# nuevo1.net
KiCad netlist of a schematic drawn in Altium Designer
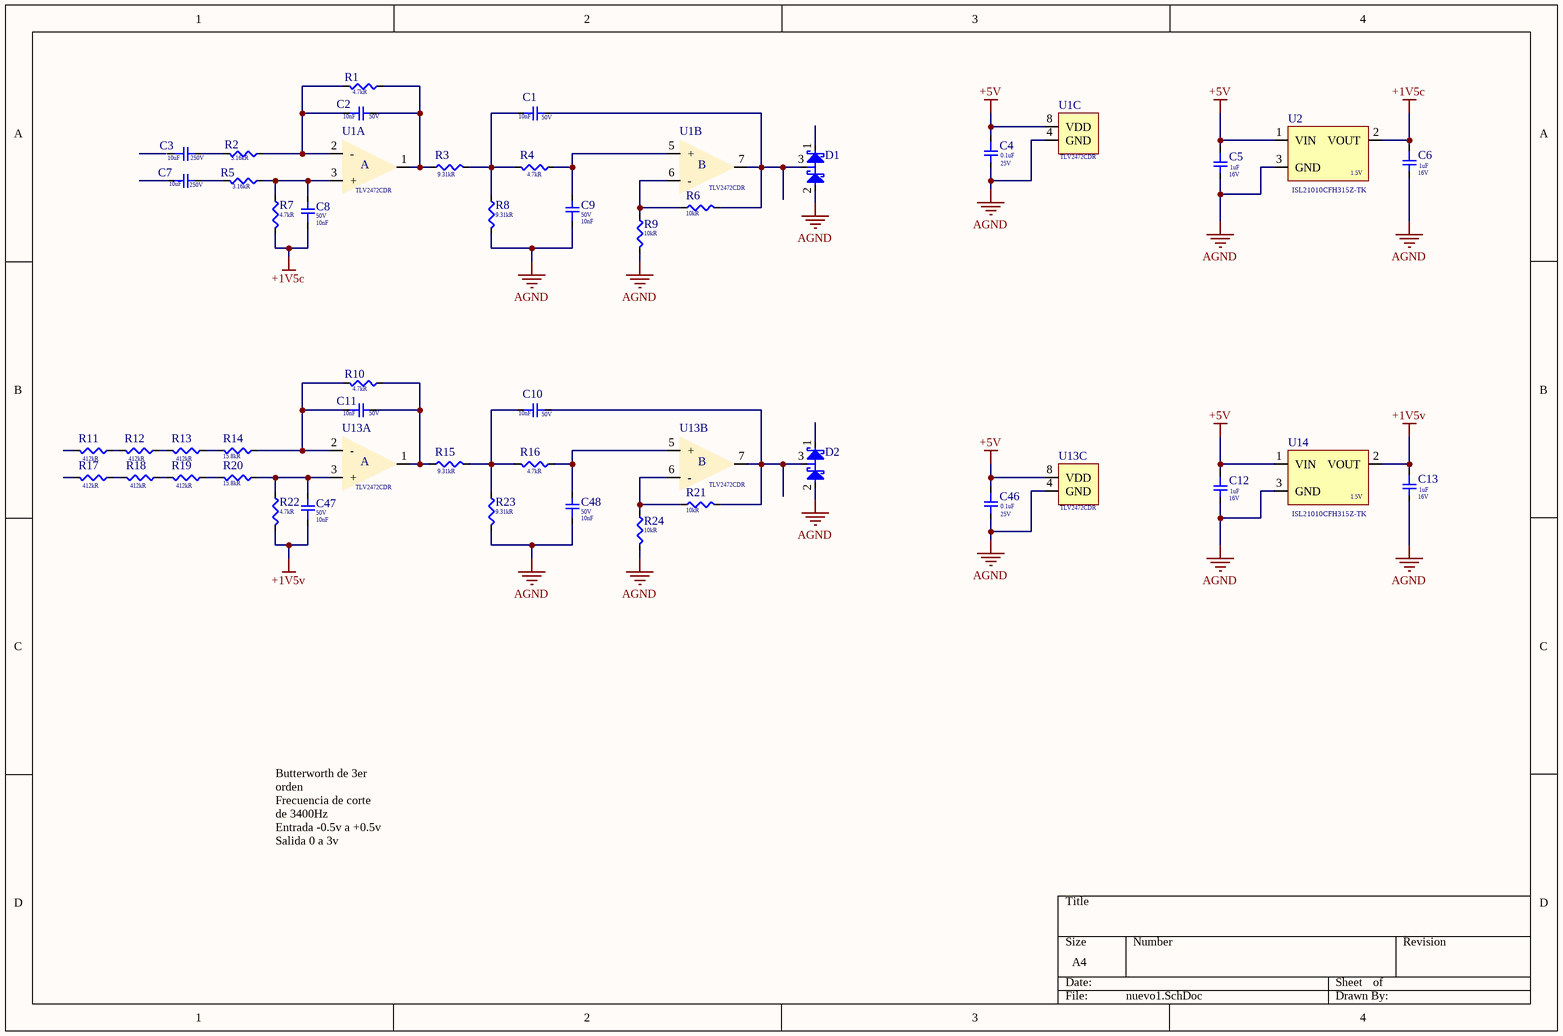
[diagram p0: nuevo1.SchDoc]

(export (version "E")
  (design (tool "Eeschema 10.0.6"))
  (components
    (comp (ref "C1")
      (value "CAP_GRM2195C1H103FA01D_MURATA")
      (footprint "CAP smd 0805")
      (description "0805 10 nF 50 V ±1% Tolerance C0G SMD Multilayer Ceramic Capacitor")
      (fields
        (field (name "TOLERANCE") "1%")
        (field (name "VOLTAGE") "50V")
        (field (name "CAPACITANCE") "10nF")
      )
      (libsource (lib "Cap") (part "CAP_GRM2195C1H103FA01D_MURATA"))
    )
    (comp (ref "C2")
      (value "CAP_GRM2195C1H103FA01D_MURATA")
      (footprint "CAP smd 0805")
      (description "0805 10 nF 50 V ±1% Tolerance C0G SMD Multilayer Ceramic Capacitor")
      (fields
        (field (name "TOLERANCE") "1%")
        (field (name "VOLTAGE") "50V")
        (field (name "CAPACITANCE") "10nF")
      )
      (libsource (lib "Cap") (part "CAP_GRM2195C1H103FA01D_MURATA"))
    )
    (comp (ref "C3")
      (value "CAP_B32754C2106K000")
      (footprint "Cap 22x36.5x31.5")
      (description "Cap Film 10uF 500V PP 10% (31.5 X 22 X 36.5mm) Dipped Radial 27.5mm 105°C Bulk")
      (fields
        (field (name "TOLERANCE") "10%")
        (field (name "VOLTAGE RATING (AC)") "250V")
        (field (name "CAPACITANCE") "10uF")
      )
      (libsource (lib "Cap") (part "CAP_B32754C2106K000"))
    )
    (comp (ref "C4")
      (value "CAP_CC0805KRX7R8BB104_YAGEO")
      (footprint "CAP smd 0805")
      (description "CAPACITOR, 0805, 100NF, 25V, REEL 4000")
      (fields
        (field (name "TOLERANCE") "10%")
        (field (name "VOLTAGE RATING") "25V")
        (field (name "CAPACITANCE") "0.1uF")
      )
      (libsource (lib "Cap") (part "CAP_CC0805KRX7R8BB104_YAGEO"))
    )
    (comp (ref "C5")
      (value "CAP_CC0805KKX7R7BB105_YAGEO")
      (footprint "CAP smd 0805")
      (description "YAGEO   CC0805KKX7R7BB105   CERAMIC CAPACITOR, 1UF, 16V, X7R, 10%, 0805")
      (fields
        (field (name "TOLERANCE") "10%")
        (field (name "VOLTAGE RATING") "16V")
        (field (name "CAPACITANCE") "1uF")
      )
      (libsource (lib "Cap") (part "CAP_CC0805KKX7R7BB105_YAGEO"))
    )
    (comp (ref "C6")
      (value "CAP_CC0805KKX7R7BB105_YAGEO")
      (footprint "CAP smd 0805")
      (description "YAGEO   CC0805KKX7R7BB105   CERAMIC CAPACITOR, 1UF, 16V, X7R, 10%, 0805")
      (fields
        (field (name "TOLERANCE") "10%")
        (field (name "VOLTAGE RATING") "16V")
        (field (name "CAPACITANCE") "1uF")
      )
      (libsource (lib "Cap") (part "CAP_CC0805KKX7R7BB105_YAGEO"))
    )
    (comp (ref "C7")
      (value "CAP_B32754C2106K000")
      (footprint "Cap 22x36.5x31.5")
      (description "Cap Film 10uF 500V PP 10% (31.5 X 22 X 36.5mm) Dipped Radial 27.5mm 105°C Bulk")
      (fields
        (field (name "TOLERANCE") "10%")
        (field (name "VOLTAGE RATING (AC)") "250V")
        (field (name "CAPACITANCE") "10uF")
      )
      (libsource (lib "Cap") (part "CAP_B32754C2106K000"))
    )
    (comp (ref "C8")
      (value "CAP_GRM2195C1H103FA01D_MURATA")
      (footprint "CAP smd 0805")
      (description "0805 10 nF 50 V ±1% Tolerance C0G SMD Multilayer Ceramic Capacitor")
      (fields
        (field (name "TOLERANCE") "1%")
        (field (name "VOLTAGE") "50V")
        (field (name "CAPACITANCE") "10nF")
      )
      (libsource (lib "Cap") (part "CAP_GRM2195C1H103FA01D_MURATA"))
    )
    (comp (ref "C9")
      (value "CAP_GRM2195C1H103FA01D_MURATA")
      (footprint "CAP smd 0805")
      (description "0805 10 nF 50 V ±1% Tolerance C0G SMD Multilayer Ceramic Capacitor")
      (fields
        (field (name "TOLERANCE") "1%")
        (field (name "VOLTAGE") "50V")
        (field (name "CAPACITANCE") "10nF")
      )
      (libsource (lib "Cap") (part "CAP_GRM2195C1H103FA01D_MURATA"))
    )
    (comp (ref "C10")
      (value "CAP_GRM2195C1H103FA01D_MURATA")
      (footprint "CAP smd 0805")
      (description "0805 10 nF 50 V ±1% Tolerance C0G SMD Multilayer Ceramic Capacitor")
      (fields
        (field (name "TOLERANCE") "1%")
        (field (name "VOLTAGE") "50V")
        (field (name "CAPACITANCE") "10nF")
      )
      (libsource (lib "Cap") (part "CAP_GRM2195C1H103FA01D_MURATA"))
    )
    (comp (ref "C11")
      (value "CAP_GRM2195C1H103FA01D_MURATA")
      (footprint "CAP smd 0805")
      (description "0805 10 nF 50 V ±1% Tolerance C0G SMD Multilayer Ceramic Capacitor")
      (fields
        (field (name "TOLERANCE") "1%")
        (field (name "VOLTAGE") "50V")
        (field (name "CAPACITANCE") "10nF")
      )
      (libsource (lib "Cap") (part "CAP_GRM2195C1H103FA01D_MURATA"))
    )
    (comp (ref "C12")
      (value "CAP_CC0805KKX7R7BB105_YAGEO")
      (footprint "CAP smd 0805")
      (description "YAGEO   CC0805KKX7R7BB105   CERAMIC CAPACITOR, 1UF, 16V, X7R, 10%, 0805")
      (fields
        (field (name "TOLERANCE") "10%")
        (field (name "VOLTAGE RATING") "16V")
        (field (name "CAPACITANCE") "1uF")
      )
      (libsource (lib "Cap") (part "CAP_CC0805KKX7R7BB105_YAGEO"))
    )
    (comp (ref "C13")
      (value "CAP_CC0805KKX7R7BB105_YAGEO")
      (footprint "CAP smd 0805")
      (description "YAGEO   CC0805KKX7R7BB105   CERAMIC CAPACITOR, 1UF, 16V, X7R, 10%, 0805")
      (fields
        (field (name "TOLERANCE") "10%")
        (field (name "VOLTAGE RATING") "16V")
        (field (name "CAPACITANCE") "1uF")
      )
      (libsource (lib "Cap") (part "CAP_CC0805KKX7R7BB105_YAGEO"))
    )
    (comp (ref "C46")
      (value "CAP_CC0805KRX7R8BB104_YAGEO")
      (footprint "CAP smd 0805")
      (description "CAPACITOR, 0805, 100NF, 25V, REEL 4000")
      (fields
        (field (name "TOLERANCE") "10%")
        (field (name "VOLTAGE RATING") "25V")
        (field (name "CAPACITANCE") "0.1uF")
      )
      (libsource (lib "Cap") (part "CAP_CC0805KRX7R8BB104_YAGEO"))
    )
    (comp (ref "C47")
      (value "CAP_GRM2195C1H103FA01D_MURATA")
      (footprint "CAP smd 0805")
      (description "0805 10 nF 50 V ±1% Tolerance C0G SMD Multilayer Ceramic Capacitor")
      (fields
        (field (name "TOLERANCE") "1%")
        (field (name "VOLTAGE") "50V")
        (field (name "CAPACITANCE") "10nF")
      )
      (libsource (lib "Cap") (part "CAP_GRM2195C1H103FA01D_MURATA"))
    )
    (comp (ref "C48")
      (value "CAP_GRM2195C1H103FA01D_MURATA")
      (footprint "CAP smd 0805")
      (description "0805 10 nF 50 V ±1% Tolerance C0G SMD Multilayer Ceramic Capacitor")
      (fields
        (field (name "TOLERANCE") "1%")
        (field (name "VOLTAGE") "50V")
        (field (name "CAPACITANCE") "10nF")
      )
      (libsource (lib "Cap") (part "CAP_GRM2195C1H103FA01D_MURATA"))
    )
    (comp (ref "D1")
      (value "BAS40-04-TP")
      (footprint "SOT-23")
      (description "DIODE ARRAY SCHOTTKY 40V SOT23")
      (libsource (lib "diode") (part "BAS40-04-TP"))
    )
    (comp (ref "D2")
      (value "BAS40-04-TP")
      (footprint "SOT-23")
      (description "DIODE ARRAY SCHOTTKY 40V SOT23")
      (libsource (lib "diode") (part "BAS40-04-TP"))
    )
    (comp (ref "R1")
      (value "RC0805FR-074K7L")
      (footprint "res 0805")
      (description "YAGEO - RC0805FR-074K7L - SMD  0805 [2012 Metric], 4.7 kohm,  125 mW")
      (fields (field (name "TOLERANCE") "1%") (field (name "RESISTANCE") "4.7kR"))
      (libsource (lib "res") (part "RC0805FR-074K7L"))
    )
    (comp (ref "R2")
      (value "RC0805FR-073K16L")
      (footprint "res 0805")
      (description "Res Thick Film smd 0805 3.16K Ohm 1% 0.125W(1/8W)")
      (fields (field (name "TOLERANCE") "1%") (field (name "RESISTANCE") "3.16kR"))
      (libsource (lib "res") (part "RC0805FR-073K16L"))
    )
    (comp (ref "R3")
      (value "RC0805FR-079K31L")
      (footprint "res 0805")
      (description "Res Thick Film smd 0805 9.31K Ohm 1% 0.125W(1/8W)")
      (fields (field (name "TOLERANCE") "1%") (field (name "RESISTANCE") "9.31kR"))
      (libsource (lib "res") (part "RC0805FR-079K31L"))
    )
    (comp (ref "R4")
      (value "RC0805FR-074K7L")
      (footprint "res 0805")
      (description "YAGEO - RC0805FR-074K7L - SMD  0805 [2012 Metric], 4.7 kohm,  125 mW")
      (fields (field (name "TOLERANCE") "1%") (field (name "RESISTANCE") "4.7kR"))
      (libsource (lib "res") (part "RC0805FR-074K7L"))
    )
    (comp (ref "R5")
      (value "RC0805FR-073K16L")
      (footprint "res 0805")
      (description "Res Thick Film smd 0805 3.16K Ohm 1% 0.125W(1/8W)")
      (fields (field (name "TOLERANCE") "1%") (field (name "RESISTANCE") "3.16kR"))
      (libsource (lib "res") (part "RC0805FR-073K16L"))
    )
    (comp (ref "R6")
      (value "RC0805FR-0710KL")
      (footprint "res 0805")
      (description "RES SMD  0805 10K OHM 1% 1/8W")
      (fields (field (name "TOLERANCE") "1%") (field (name "RESISTANCE") "10kR"))
      (libsource (lib "res") (part "RC0805FR-0710KL"))
    )
    (comp (ref "R7")
      (value "RC0805FR-074K7L")
      (footprint "res 0805")
      (description "YAGEO - RC0805FR-074K7L - SMD  0805 [2012 Metric], 4.7 kohm,  125 mW")
      (fields (field (name "TOLERANCE") "1%") (field (name "RESISTANCE") "4.7kR"))
      (libsource (lib "res") (part "RC0805FR-074K7L"))
    )
    (comp (ref "R8")
      (value "RC0805FR-079K31L")
      (footprint "res 0805")
      (description "Res Thick Film smd 0805 9.31K Ohm 1% 0.125W(1/8W)")
      (fields (field (name "TOLERANCE") "1%") (field (name "RESISTANCE") "9.31kR"))
      (libsource (lib "res") (part "RC0805FR-079K31L"))
    )
    (comp (ref "R9")
      (value "RC0805FR-0710KL")
      (footprint "res 0805")
      (description "RES SMD  0805 10K OHM 1% 1/8W")
      (fields (field (name "TOLERANCE") "1%") (field (name "RESISTANCE") "10kR"))
      (libsource (lib "res") (part "RC0805FR-0710KL"))
    )
    (comp (ref "R10")
      (value "RC0805FR-074K7L")
      (footprint "res 0805")
      (description "YAGEO - RC0805FR-074K7L - SMD  0805 [2012 Metric], 4.7 kohm,  125 mW")
      (fields (field (name "TOLERANCE") "1%") (field (name "RESISTANCE") "4.7kR"))
      (libsource (lib "res") (part "RC0805FR-074K7L"))
    )
    (comp (ref "R11")
      (value "RC0805FR-07412KL")
      (footprint "res 0805")
      (description "RES SMD 0805 412K OHM 1% 1/8W")
      (fields (field (name "TOLERANCE") "1%") (field (name "RESISTANCE") "412kR"))
      (libsource (lib "res") (part "RC0805FR-07412KL"))
    )
    (comp (ref "R12")
      (value "RC0805FR-07412KL")
      (footprint "res 0805")
      (description "RES SMD 0805 412K OHM 1% 1/8W")
      (fields (field (name "TOLERANCE") "1%") (field (name "RESISTANCE") "412kR"))
      (libsource (lib "res") (part "RC0805FR-07412KL"))
    )
    (comp (ref "R13")
      (value "RC0805FR-07412KL")
      (footprint "res 0805")
      (description "RES SMD 0805 412K OHM 1% 1/8W")
      (fields (field (name "TOLERANCE") "1%") (field (name "RESISTANCE") "412kR"))
      (libsource (lib "res") (part "RC0805FR-07412KL"))
    )
    (comp (ref "R14")
      (value "RC0805FR-0715K8L")
      (footprint "res 0805")
      (description "Res Thick Film smd 0805 15.8K Ohm 1% 0.125W(1/8W)")
      (fields (field (name "TOLERANCE") "1%") (field (name "RESISTANCE") "15.8kR"))
      (libsource (lib "res") (part "RC0805FR-0715K8L"))
    )
    (comp (ref "R15")
      (value "RC0805FR-079K31L")
      (footprint "res 0805")
      (description "Res Thick Film smd 0805 9.31K Ohm 1% 0.125W(1/8W)")
      (fields (field (name "TOLERANCE") "1%") (field (name "RESISTANCE") "9.31kR"))
      (libsource (lib "res") (part "RC0805FR-079K31L"))
    )
    (comp (ref "R16")
      (value "RC0805FR-074K7L")
      (footprint "res 0805")
      (description "YAGEO - RC0805FR-074K7L - SMD  0805 [2012 Metric], 4.7 kohm,  125 mW")
      (fields (field (name "TOLERANCE") "1%") (field (name "RESISTANCE") "4.7kR"))
      (libsource (lib "res") (part "RC0805FR-074K7L"))
    )
    (comp (ref "R17")
      (value "RC0805FR-07412KL")
      (footprint "res 0805")
      (description "RES SMD 0805 412K OHM 1% 1/8W")
      (fields (field (name "TOLERANCE") "1%") (field (name "RESISTANCE") "412kR"))
      (libsource (lib "res") (part "RC0805FR-07412KL"))
    )
    (comp (ref "R18")
      (value "RC0805FR-07412KL")
      (footprint "res 0805")
      (description "RES SMD 0805 412K OHM 1% 1/8W")
      (fields (field (name "TOLERANCE") "1%") (field (name "RESISTANCE") "412kR"))
      (libsource (lib "res") (part "RC0805FR-07412KL"))
    )
    (comp (ref "R19")
      (value "RC0805FR-07412KL")
      (footprint "res 0805")
      (description "RES SMD 0805 412K OHM 1% 1/8W")
      (fields (field (name "TOLERANCE") "1%") (field (name "RESISTANCE") "412kR"))
      (libsource (lib "res") (part "RC0805FR-07412KL"))
    )
    (comp (ref "R20")
      (value "RC0805FR-0715K8L")
      (footprint "res 0805")
      (description "Res Thick Film smd 0805 15.8K Ohm 1% 0.125W(1/8W)")
      (fields (field (name "TOLERANCE") "1%") (field (name "RESISTANCE") "15.8kR"))
      (libsource (lib "res") (part "RC0805FR-0715K8L"))
    )
    (comp (ref "R21")
      (value "RC0805FR-0710KL")
      (footprint "res 0805")
      (description "RES SMD  0805 10K OHM 1% 1/8W")
      (fields (field (name "TOLERANCE") "1%") (field (name "RESISTANCE") "10kR"))
      (libsource (lib "res") (part "RC0805FR-0710KL"))
    )
    (comp (ref "R22")
      (value "RC0805FR-074K7L")
      (footprint "res 0805")
      (description "YAGEO - RC0805FR-074K7L - SMD  0805 [2012 Metric], 4.7 kohm,  125 mW")
      (fields (field (name "TOLERANCE") "1%") (field (name "RESISTANCE") "4.7kR"))
      (libsource (lib "res") (part "RC0805FR-074K7L"))
    )
    (comp (ref "R23")
      (value "RC0805FR-079K31L")
      (footprint "res 0805")
      (description "Res Thick Film smd 0805 9.31K Ohm 1% 0.125W(1/8W)")
      (fields (field (name "TOLERANCE") "1%") (field (name "RESISTANCE") "9.31kR"))
      (libsource (lib "res") (part "RC0805FR-079K31L"))
    )
    (comp (ref "R24")
      (value "RC0805FR-0710KL")
      (footprint "res 0805")
      (description "RES SMD  0805 10K OHM 1% 1/8W")
      (fields (field (name "TOLERANCE") "1%") (field (name "RESISTANCE") "10kR"))
      (libsource (lib "res") (part "RC0805FR-0710KL"))
    )
    (comp (ref "U1")
      (value "TLV2472CDR")
      (description "IC OPAMP GP 2.8MHZ RRO 8SOIC")
      (libsource (lib "ic") (part "TLV2472CDR"))
    )
    (comp (ref "U2")
      (value "ISL21010CFH315Z-TK")
      (fields
        (field (name "TOLERANCE") "0.2%")
        (field (name "MANUFACTURER PART NUMBER 1") "ISL21010CFH315Z-TK")
        (field (name "REFERENCE VOLTAGE") "1.5V")
      )
      (libsource (lib "ic") (part "ISL21010CFH315Z-TK"))
    )
    (comp (ref "U13")
      (value "TLV2472CDR")
      (description "IC OPAMP GP 2.8MHZ RRO 8SOIC")
      (libsource (lib "ic") (part "TLV2472CDR"))
    )
    (comp (ref "U14")
      (value "ISL21010CFH315Z-TK")
      (fields
        (field (name "TOLERANCE") "0.2%")
        (field (name "MANUFACTURER PART NUMBER 1") "ISL21010CFH315Z-TK")
        (field (name "REFERENCE VOLTAGE") "1.5V")
      )
      (libsource (lib "ic") (part "ISL21010CFH315Z-TK"))
    )
  )
  (nets
    (net (code "1") (name "+1V5c") (class "Default")
      (node (ref "C6") (pin "23") (pinfunction "23_23") (pintype "passive"))
      (node (ref "C8") (pin "23") (pinfunction "23_23") (pintype "passive"))
      (node (ref "R7") (pin "2") (pinfunction "2_2") (pintype "passive"))
      (node (ref "U2") (pin "2") (pinfunction "VOUT_2") (pintype "passive"))
    )
    (net (code "2") (name "+1V5v") (class "Default")
      (node (ref "C13") (pin "23") (pinfunction "23_23") (pintype "passive"))
      (node (ref "C47") (pin "23") (pinfunction "23_23") (pintype "passive"))
      (node (ref "R22") (pin "2") (pinfunction "2_2") (pintype "passive"))
      (node (ref "U14") (pin "2") (pinfunction "VOUT_2") (pintype "passive"))
    )
    (net (code "3") (name "+5V") (class "Default")
      (node (ref "C12") (pin "23") (pinfunction "23_23") (pintype "passive"))
      (node (ref "C4") (pin "23") (pinfunction "23_23") (pintype "passive"))
      (node (ref "C46") (pin "23") (pinfunction "23_23") (pintype "passive"))
      (node (ref "C5") (pin "23") (pinfunction "23_23") (pintype "passive"))
      (node (ref "U1") (pin "8") (pinfunction "VDD_8") (pintype "passive"))
      (node (ref "U13") (pin "8") (pinfunction "VDD_8") (pintype "passive"))
      (node (ref "U14") (pin "1") (pinfunction "VIN_1") (pintype "passive"))
      (node (ref "U2") (pin "1") (pinfunction "VIN_1") (pintype "passive"))
    )
    (net (code "4") (name "AGND") (class "Default")
      (node (ref "C12") (pin "22") (pinfunction "22_22") (pintype "passive"))
      (node (ref "C13") (pin "22") (pinfunction "22_22") (pintype "passive"))
      (node (ref "C4") (pin "22") (pinfunction "22_22") (pintype "passive"))
      (node (ref "C46") (pin "22") (pinfunction "22_22") (pintype "passive"))
      (node (ref "C48") (pin "23") (pinfunction "23_23") (pintype "passive"))
      (node (ref "C5") (pin "22") (pinfunction "22_22") (pintype "passive"))
      (node (ref "C6") (pin "22") (pinfunction "22_22") (pintype "passive"))
      (node (ref "C9") (pin "23") (pinfunction "23_23") (pintype "passive"))
      (node (ref "D1") (pin "2") (pinfunction "2_2") (pintype "passive"))
      (node (ref "D2") (pin "2") (pinfunction "2_2") (pintype "passive"))
      (node (ref "R23") (pin "2") (pinfunction "2_2") (pintype "passive"))
      (node (ref "R24") (pin "2") (pinfunction "2_2") (pintype "passive"))
      (node (ref "R8") (pin "2") (pinfunction "2_2") (pintype "passive"))
      (node (ref "R9") (pin "2") (pinfunction "2_2") (pintype "passive"))
      (node (ref "U1") (pin "4") (pinfunction "GND_4") (pintype "passive"))
      (node (ref "U13") (pin "4") (pinfunction "GND_4") (pintype "passive"))
      (node (ref "U14") (pin "3") (pinfunction "GND_3") (pintype "passive"))
      (node (ref "U2") (pin "3") (pinfunction "GND_3") (pintype "passive"))
    )
    (net (code "5") (name "Net-(C1-Pad22)") (class "Default")
      (node (ref "C1") (pin "22") (pinfunction "22_22") (pintype "passive"))
      (node (ref "D1") (pin "3") (pinfunction "3_3") (pintype "passive"))
      (node (ref "R6") (pin "2") (pinfunction "2_2") (pintype "passive"))
      (node (ref "U1") (pin "7") (pinfunction "7_7") (pintype "passive"))
    )
    (net (code "6") (name "Net-(C1-Pad23)") (class "Default")
      (node (ref "C1") (pin "23") (pinfunction "23_23") (pintype "passive"))
      (node (ref "R3") (pin "2") (pinfunction "2_2") (pintype "passive"))
      (node (ref "R4") (pin "2") (pinfunction "2_2") (pintype "passive"))
      (node (ref "R8") (pin "1") (pinfunction "1_1") (pintype "passive"))
    )
    (net (code "7") (name "Net-(C2-Pad22)") (class "Default")
      (node (ref "C2") (pin "22") (pinfunction "22_22") (pintype "passive"))
      (node (ref "R1") (pin "1") (pinfunction "1_1") (pintype "passive"))
      (node (ref "R3") (pin "1") (pinfunction "1_1") (pintype "passive"))
      (node (ref "U1") (pin "1") (pinfunction "1_1") (pintype "passive"))
    )
    (net (code "8") (name "Net-(C3-Pad22)") (class "Default")
      (node (ref "C3") (pin "22") (pinfunction "22_22") (pintype "passive"))
      (node (ref "R2") (pin "1") (pinfunction "1_1") (pintype "passive"))
    )
    (net (code "9") (name "Net-(C7-Pad22)") (class "Default")
      (node (ref "C7") (pin "22") (pinfunction "22_22") (pintype "passive"))
      (node (ref "R5") (pin "1") (pinfunction "1_1") (pintype "passive"))
    )
    (net (code "10") (name "Net-(C10-Pad22)") (class "Default")
      (node (ref "C10") (pin "22") (pinfunction "22_22") (pintype "passive"))
      (node (ref "D2") (pin "3") (pinfunction "3_3") (pintype "passive"))
      (node (ref "R21") (pin "2") (pinfunction "2_2") (pintype "passive"))
      (node (ref "U13") (pin "7") (pinfunction "7_7") (pintype "passive"))
    )
    (net (code "11") (name "Net-(C10-Pad23)") (class "Default")
      (node (ref "C10") (pin "23") (pinfunction "23_23") (pintype "passive"))
      (node (ref "R15") (pin "2") (pinfunction "2_2") (pintype "passive"))
      (node (ref "R16") (pin "2") (pinfunction "2_2") (pintype "passive"))
      (node (ref "R23") (pin "1") (pinfunction "1_1") (pintype "passive"))
    )
    (net (code "12") (name "Net-(C11-Pad22)") (class "Default")
      (node (ref "C11") (pin "22") (pinfunction "22_22") (pintype "passive"))
      (node (ref "R10") (pin "1") (pinfunction "1_1") (pintype "passive"))
      (node (ref "R15") (pin "1") (pinfunction "1_1") (pintype "passive"))
      (node (ref "U13") (pin "1") (pinfunction "1_1") (pintype "passive"))
    )
    (net (code "13") (name "Net-(R11-Pad1)") (class "Default")
      (node (ref "R11") (pin "1") (pinfunction "1_1") (pintype "passive"))
      (node (ref "R12") (pin "2") (pinfunction "2_2") (pintype "passive"))
    )
    (net (code "14") (name "Net-(R12-Pad1)") (class "Default")
      (node (ref "R12") (pin "1") (pinfunction "1_1") (pintype "passive"))
      (node (ref "R13") (pin "2") (pinfunction "2_2") (pintype "passive"))
    )
    (net (code "15") (name "Net-(R13-Pad1)") (class "Default")
      (node (ref "R13") (pin "1") (pinfunction "1_1") (pintype "passive"))
      (node (ref "R14") (pin "2") (pinfunction "2_2") (pintype "passive"))
    )
    (net (code "16") (name "Net-(R17-Pad1)") (class "Default")
      (node (ref "R17") (pin "1") (pinfunction "1_1") (pintype "passive"))
      (node (ref "R18") (pin "2") (pinfunction "2_2") (pintype "passive"))
    )
    (net (code "17") (name "Net-(R18-Pad1)") (class "Default")
      (node (ref "R18") (pin "1") (pinfunction "1_1") (pintype "passive"))
      (node (ref "R19") (pin "2") (pinfunction "2_2") (pintype "passive"))
    )
    (net (code "18") (name "Net-(R19-Pad1)") (class "Default")
      (node (ref "R19") (pin "1") (pinfunction "1_1") (pintype "passive"))
      (node (ref "R20") (pin "2") (pinfunction "2_2") (pintype "passive"))
    )
    (net (code "19") (name "Net-(U1A-+)") (class "Default")
      (node (ref "C8") (pin "22") (pinfunction "22_22") (pintype "passive"))
      (node (ref "R5") (pin "2") (pinfunction "2_2") (pintype "passive"))
      (node (ref "R7") (pin "1") (pinfunction "1_1") (pintype "passive"))
      (node (ref "U1") (pin "3") (pinfunction "+_3") (pintype "passive"))
    )
    (net (code "20") (name "Net-(U1A--)") (class "Default")
      (node (ref "C2") (pin "23") (pinfunction "23_23") (pintype "passive"))
      (node (ref "R1") (pin "2") (pinfunction "2_2") (pintype "passive"))
      (node (ref "R2") (pin "2") (pinfunction "2_2") (pintype "passive"))
      (node (ref "U1") (pin "2") (pinfunction "-_2") (pintype "passive"))
    )
    (net (code "21") (name "Net-(U1B-+)") (class "Default")
      (node (ref "C9") (pin "22") (pinfunction "22_22") (pintype "passive"))
      (node (ref "R4") (pin "1") (pinfunction "1_1") (pintype "passive"))
      (node (ref "U1") (pin "5") (pinfunction "+_5") (pintype "passive"))
    )
    (net (code "22") (name "Net-(U1B--)") (class "Default")
      (node (ref "R6") (pin "1") (pinfunction "1_1") (pintype "passive"))
      (node (ref "R9") (pin "1") (pinfunction "1_1") (pintype "passive"))
      (node (ref "U1") (pin "6") (pinfunction "-_6") (pintype "passive"))
    )
    (net (code "23") (name "Net-(U13A-+)") (class "Default")
      (node (ref "C47") (pin "22") (pinfunction "22_22") (pintype "passive"))
      (node (ref "R20") (pin "1") (pinfunction "1_1") (pintype "passive"))
      (node (ref "R22") (pin "1") (pinfunction "1_1") (pintype "passive"))
      (node (ref "U13") (pin "3") (pinfunction "+_3") (pintype "passive"))
    )
    (net (code "24") (name "Net-(U13A--)") (class "Default")
      (node (ref "C11") (pin "23") (pinfunction "23_23") (pintype "passive"))
      (node (ref "R10") (pin "2") (pinfunction "2_2") (pintype "passive"))
      (node (ref "R14") (pin "1") (pinfunction "1_1") (pintype "passive"))
      (node (ref "U13") (pin "2") (pinfunction "-_2") (pintype "passive"))
    )
    (net (code "25") (name "Net-(U13B-+)") (class "Default")
      (node (ref "C48") (pin "22") (pinfunction "22_22") (pintype "passive"))
      (node (ref "R16") (pin "1") (pinfunction "1_1") (pintype "passive"))
      (node (ref "U13") (pin "5") (pinfunction "+_5") (pintype "passive"))
    )
    (net (code "26") (name "Net-(U13B--)") (class "Default")
      (node (ref "R21") (pin "1") (pinfunction "1_1") (pintype "passive"))
      (node (ref "R24") (pin "1") (pinfunction "1_1") (pintype "passive"))
      (node (ref "U13") (pin "6") (pinfunction "-_6") (pintype "passive"))
    )
    (net (code "27") (name "unconnected-(C3-Pad23)") (class "Default")
      (node (ref "C3") (pin "23") (pinfunction "23_23") (pintype "passive"))
    )
    (net (code "28") (name "unconnected-(C7-Pad23)") (class "Default")
      (node (ref "C7") (pin "23") (pinfunction "23_23") (pintype "passive"))
    )
    (net (code "29") (name "unconnected-(D1-Pad1)") (class "Default")
      (node (ref "D1") (pin "1") (pinfunction "1_1") (pintype "passive"))
    )
    (net (code "30") (name "unconnected-(D2-Pad1)") (class "Default")
      (node (ref "D2") (pin "1") (pinfunction "1_1") (pintype "passive"))
    )
    (net (code "31") (name "unconnected-(R11-Pad2)") (class "Default")
      (node (ref "R11") (pin "2") (pinfunction "2_2") (pintype "passive"))
    )
    (net (code "32") (name "unconnected-(R17-Pad2)") (class "Default")
      (node (ref "R17") (pin "2") (pinfunction "2_2") (pintype "passive"))
    )
  )
)
